# Senser.net
KiCad netlist of a schematic drawn in Altium Designer
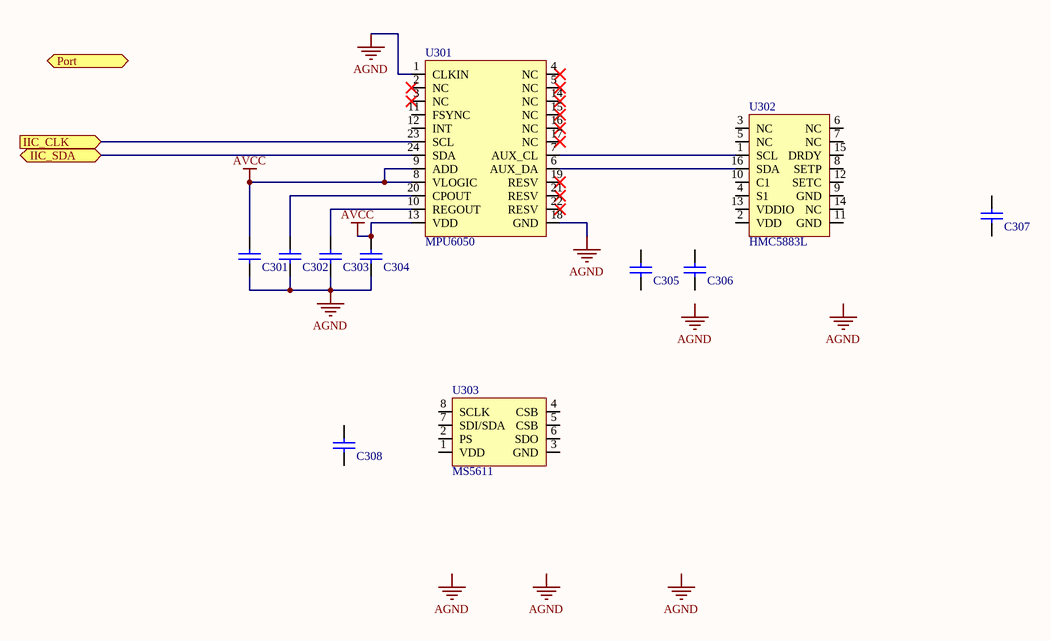
[diagram p0: Senser.SchDoc]

(export (version "E")
  (design (tool "Eeschema 10.0.6"))
  (components
    (comp (ref "C301") (value "Cap 0603") (libsource (lib "Quadcopter") (part "Cap 0603")))
    (comp (ref "C302") (value "Cap 0603") (libsource (lib "Quadcopter") (part "Cap 0603")))
    (comp (ref "C303") (value "Cap 0603") (libsource (lib "Quadcopter") (part "Cap 0603")))
    (comp (ref "C304") (value "Cap 0603") (libsource (lib "Quadcopter") (part "Cap 0603")))
    (comp (ref "C305") (value "Cap 0603") (libsource (lib "Quadcopter") (part "Cap 0603")))
    (comp (ref "C306") (value "Cap 0603") (libsource (lib "Quadcopter") (part "Cap 0603")))
    (comp (ref "C307") (value "Cap 0603") (libsource (lib "Quadcopter") (part "Cap 0603")))
    (comp (ref "C308") (value "Cap 0603") (libsource (lib "Quadcopter") (part "Cap 0603")))
    (comp (ref "U301") (value "MPU6050") (libsource (lib "Quadcopter") (part "MPU6050")))
    (comp (ref "U302") (value "HMC5883L") (libsource (lib "Quadcopter") (part "HMC5883L")))
    (comp (ref "U303") (value "MS5611") (libsource (lib "Quadcopter") (part "MS5611")))
  )
  (nets
    (net (code "1") (name "/IIC_CLK") (class "Default")
      (node (ref "U301") (pin "23") (pinfunction "SCL_23") (pintype "passive"))
    )
    (net (code "2") (name "/IIC_SDA") (class "Default")
      (node (ref "U301") (pin "24") (pinfunction "SDA_24") (pintype "passive"))
    )
    (net (code "4") (name "AGND") (class "Default")
      (node (ref "C301") (pin "1") (pinfunction "1_1") (pintype "passive"))
      (node (ref "C302") (pin "1") (pinfunction "1_1") (pintype "passive"))
      (node (ref "C303") (pin "1") (pinfunction "1_1") (pintype "passive"))
      (node (ref "C304") (pin "1") (pinfunction "1_1") (pintype "passive"))
      (node (ref "U301") (pin "1") (pinfunction "CLKIN_1") (pintype "passive"))
      (node (ref "U301") (pin "18") (pinfunction "GND_18") (pintype "passive"))
    )
    (net (code "5") (name "AVCC") (class "Default")
      (node (ref "C301") (pin "2") (pinfunction "2_2") (pintype "passive"))
      (node (ref "C304") (pin "2") (pinfunction "2_2") (pintype "passive"))
      (node (ref "U301") (pin "13") (pinfunction "VDD_13") (pintype "passive"))
      (node (ref "U301") (pin "8") (pinfunction "VLOGIC_8") (pintype "passive"))
      (node (ref "U301") (pin "9") (pinfunction "ADD_9") (pintype "passive"))
    )
    (net (code "6") (name "Net-(U301-AUX_CL)") (class "Default")
      (node (ref "U301") (pin "7") (pinfunction "AUX_CL_7") (pintype "passive"))
      (node (ref "U302") (pin "1") (pinfunction "SCL_1") (pintype "passive"))
    )
    (net (code "7") (name "Net-(U301-AUX_DA)") (class "Default")
      (node (ref "U301") (pin "6") (pinfunction "AUX_DA_6") (pintype "passive"))
      (node (ref "U302") (pin "16") (pinfunction "SDA_16") (pintype "passive"))
    )
    (net (code "8") (name "Net-(U301-CPOUT)") (class "Default")
      (node (ref "C302") (pin "2") (pinfunction "2_2") (pintype "passive"))
      (node (ref "U301") (pin "20") (pinfunction "CPOUT_20") (pintype "passive"))
    )
    (net (code "9") (name "Net-(U301-REGOUT)") (class "Default")
      (node (ref "C303") (pin "2") (pinfunction "2_2") (pintype "passive"))
      (node (ref "U301") (pin "10") (pinfunction "REGOUT_10") (pintype "passive"))
    )
    (net (code "10") (name "unconnected-(C305-Pad1)") (class "Default")
      (node (ref "C305") (pin "1") (pinfunction "1_1") (pintype "passive"))
    )
    (net (code "11") (name "unconnected-(C305-Pad2)") (class "Default")
      (node (ref "C305") (pin "2") (pinfunction "2_2") (pintype "passive"))
    )
    (net (code "12") (name "unconnected-(C306-Pad1)") (class "Default")
      (node (ref "C306") (pin "1") (pinfunction "1_1") (pintype "passive"))
    )
    (net (code "13") (name "unconnected-(C306-Pad2)") (class "Default")
      (node (ref "C306") (pin "2") (pinfunction "2_2") (pintype "passive"))
    )
    (net (code "14") (name "unconnected-(C307-Pad1)") (class "Default")
      (node (ref "C307") (pin "1") (pinfunction "1_1") (pintype "passive"))
    )
    (net (code "15") (name "unconnected-(C307-Pad2)") (class "Default")
      (node (ref "C307") (pin "2") (pinfunction "2_2") (pintype "passive"))
    )
    (net (code "16") (name "unconnected-(C308-Pad1)") (class "Default")
      (node (ref "C308") (pin "1") (pinfunction "1_1") (pintype "passive"))
    )
    (net (code "17") (name "unconnected-(C308-Pad2)") (class "Default")
      (node (ref "C308") (pin "2") (pinfunction "2_2") (pintype "passive"))
    )
    (net (code "18") (name "unconnected-(U301-FSYNC-Pad11)") (class "Default")
      (node (ref "U301") (pin "11") (pinfunction "FSYNC_11") (pintype "passive"))
    )
    (net (code "19") (name "unconnected-(U301-INT-Pad12)") (class "Default")
      (node (ref "U301") (pin "12") (pinfunction "INT_12") (pintype "passive"))
    )
    (net (code "20") (name "unconnected-(U301-NC-Pad2)") (class "Default")
      (node (ref "U301") (pin "2") (pinfunction "NC_2") (pintype "passive+no_connect"))
    )
    (net (code "21") (name "unconnected-(U301-NC-Pad3)") (class "Default")
      (node (ref "U301") (pin "3") (pinfunction "NC_3") (pintype "passive+no_connect"))
    )
    (net (code "22") (name "unconnected-(U301-NC-Pad4)") (class "Default")
      (node (ref "U301") (pin "4") (pinfunction "NC_4") (pintype "passive+no_connect"))
    )
    (net (code "23") (name "unconnected-(U301-NC-Pad5)") (class "Default")
      (node (ref "U301") (pin "5") (pinfunction "NC_5") (pintype "passive+no_connect"))
    )
    (net (code "24") (name "unconnected-(U301-NC-Pad14)") (class "Default")
      (node (ref "U301") (pin "14") (pinfunction "NC_14") (pintype "passive+no_connect"))
    )
    (net (code "25") (name "unconnected-(U301-NC-Pad15)") (class "Default")
      (node (ref "U301") (pin "15") (pinfunction "NC_15") (pintype "passive+no_connect"))
    )
    (net (code "26") (name "unconnected-(U301-NC-Pad16)") (class "Default")
      (node (ref "U301") (pin "16") (pinfunction "NC_16") (pintype "passive+no_connect"))
    )
    (net (code "27") (name "unconnected-(U301-NC-Pad17)") (class "Default")
      (node (ref "U301") (pin "17") (pinfunction "NC_17") (pintype "passive+no_connect"))
    )
    (net (code "28") (name "unconnected-(U301-RESV-Pad19)") (class "Default")
      (node (ref "U301") (pin "19") (pinfunction "RESV_19") (pintype "passive+no_connect"))
    )
    (net (code "29") (name "unconnected-(U301-RESV-Pad21)") (class "Default")
      (node (ref "U301") (pin "21") (pinfunction "RESV_21") (pintype "passive+no_connect"))
    )
    (net (code "30") (name "unconnected-(U301-RESV-Pad22)") (class "Default")
      (node (ref "U301") (pin "22") (pinfunction "RESV_22") (pintype "passive+no_connect"))
    )
    (net (code "31") (name "unconnected-(U302-C1-Pad10)") (class "Default")
      (node (ref "U302") (pin "10") (pinfunction "C1_10") (pintype "passive"))
    )
    (net (code "32") (name "unconnected-(U302-DRDY-Pad15)") (class "Default")
      (node (ref "U302") (pin "15") (pinfunction "DRDY_15") (pintype "passive"))
    )
    (net (code "33") (name "unconnected-(U302-GND-Pad9)") (class "Default")
      (node (ref "U302") (pin "9") (pinfunction "GND_9") (pintype "passive"))
    )
    (net (code "34") (name "unconnected-(U302-GND-Pad11)") (class "Default")
      (node (ref "U302") (pin "11") (pinfunction "GND_11") (pintype "passive"))
    )
    (net (code "35") (name "unconnected-(U302-NC-Pad3)") (class "Default")
      (node (ref "U302") (pin "3") (pinfunction "NC_3") (pintype "passive"))
    )
    (net (code "36") (name "unconnected-(U302-NC-Pad5)") (class "Default")
      (node (ref "U302") (pin "5") (pinfunction "NC_5") (pintype "passive"))
    )
    (net (code "37") (name "unconnected-(U302-NC-Pad6)") (class "Default")
      (node (ref "U302") (pin "6") (pinfunction "NC_6") (pintype "passive"))
    )
    (net (code "38") (name "unconnected-(U302-NC-Pad7)") (class "Default")
      (node (ref "U302") (pin "7") (pinfunction "NC_7") (pintype "passive"))
    )
    (net (code "39") (name "unconnected-(U302-NC-Pad14)") (class "Default")
      (node (ref "U302") (pin "14") (pinfunction "NC_14") (pintype "passive"))
    )
    (net (code "40") (name "unconnected-(U302-S1-Pad4)") (class "Default")
      (node (ref "U302") (pin "4") (pinfunction "S1_4") (pintype "passive"))
    )
    (net (code "41") (name "unconnected-(U302-SETC-Pad12)") (class "Default")
      (node (ref "U302") (pin "12") (pinfunction "SETC_12") (pintype "passive"))
    )
    (net (code "42") (name "unconnected-(U302-SETP-Pad8)") (class "Default")
      (node (ref "U302") (pin "8") (pinfunction "SETP_8") (pintype "passive"))
    )
    (net (code "43") (name "unconnected-(U302-VDD-Pad2)") (class "Default")
      (node (ref "U302") (pin "2") (pinfunction "VDD_2") (pintype "passive"))
    )
    (net (code "44") (name "unconnected-(U302-VDDIO-Pad13)") (class "Default")
      (node (ref "U302") (pin "13") (pinfunction "VDDIO_13") (pintype "passive"))
    )
    (net (code "45") (name "unconnected-(U303-CSB-Pad4)") (class "Default")
      (node (ref "U303") (pin "4") (pinfunction "CSB_4") (pintype "passive"))
    )
    (net (code "46") (name "unconnected-(U303-CSB-Pad5)") (class "Default")
      (node (ref "U303") (pin "5") (pinfunction "CSB_5") (pintype "passive"))
    )
    (net (code "47") (name "unconnected-(U303-GND-Pad3)") (class "Default")
      (node (ref "U303") (pin "3") (pinfunction "GND_3") (pintype "passive"))
    )
    (net (code "48") (name "unconnected-(U303-PS-Pad2)") (class "Default")
      (node (ref "U303") (pin "2") (pinfunction "PS_2") (pintype "passive"))
    )
    (net (code "49") (name "unconnected-(U303-SCLK-Pad8)") (class "Default")
      (node (ref "U303") (pin "8") (pinfunction "SCLK_8") (pintype "passive"))
    )
    (net (code "50") (name "unconnected-(U303-SDI{slash}SDA-Pad7)") (class "Default")
      (node (ref "U303") (pin "7") (pinfunction "SDI/SDA_7") (pintype "passive"))
    )
    (net (code "51") (name "unconnected-(U303-SDO-Pad6)") (class "Default")
      (node (ref "U303") (pin "6") (pinfunction "SDO_6") (pintype "passive"))
    )
    (net (code "52") (name "unconnected-(U303-VDD-Pad1)") (class "Default")
      (node (ref "U303") (pin "1") (pinfunction "VDD_1") (pintype "passive"))
    )
  )
)
